# N2a.net
KiCad netlist of a schematic drawn in EAGLE
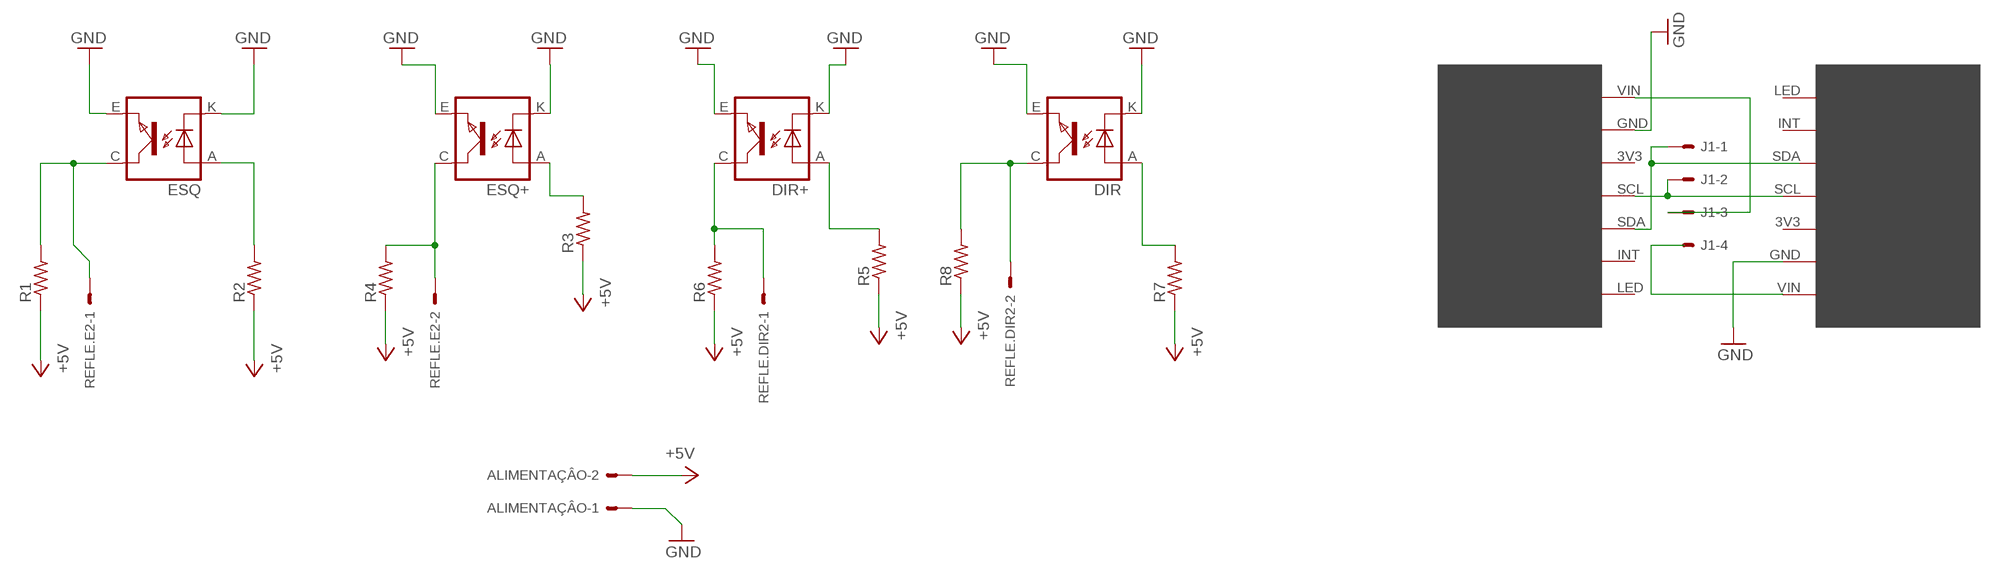
[diagram p0: schematic, sheet 1]

(export (version "E")
  (design (tool "Eeschema 10.0.6"))
  (components
    (comp (ref "ALIMENTAÇÂO")
      (value "CONN_0205-7028")
      (footprint "eagle-import:7395-02")
      (libsource (lib "eagle-import") (part "CONN_0205-7028"))
    )
    (comp (ref "DIR")
      (value "TCRT5000")
      (footprint "eagle-import:TCRT5000")
      (libsource (lib "eagle-import") (part "TCRT5000"))
    )
    (comp (ref "DIR+")
      (value "TCRT5000")
      (footprint "eagle-import:TCRT5000")
      (libsource (lib "eagle-import") (part "TCRT5000"))
    )
    (comp (ref "ESQ")
      (value "TCRT5000")
      (footprint "eagle-import:TCRT5000")
      (libsource (lib "eagle-import") (part "TCRT5000"))
    )
    (comp (ref "ESQ+")
      (value "TCRT5000")
      (footprint "eagle-import:TCRT5000")
      (libsource (lib "eagle-import") (part "TCRT5000"))
    )
    (comp (ref "J1")
      (value "CONN_0405-7048")
      (footprint "eagle-import:7395-04")
      (libsource (lib "eagle-import") (part "CONN_0405-7048"))
    )
    (comp (ref "R1")
      (value "R-US_0204/7")
      (footprint "eagle-import:0204_7")
      (libsource (lib "eagle-import") (part "R-US_0204/7"))
    )
    (comp (ref "R2")
      (value "R-US_0204/7")
      (footprint "eagle-import:0204_7")
      (libsource (lib "eagle-import") (part "R-US_0204/7"))
    )
    (comp (ref "R3")
      (value "R-US_0204/7")
      (footprint "eagle-import:0204_7")
      (libsource (lib "eagle-import") (part "R-US_0204/7"))
    )
    (comp (ref "R4")
      (value "R-US_0204/7")
      (footprint "eagle-import:0204_7")
      (libsource (lib "eagle-import") (part "R-US_0204/7"))
    )
    (comp (ref "R5")
      (value "R-US_0204/7")
      (footprint "eagle-import:0204_7")
      (libsource (lib "eagle-import") (part "R-US_0204/7"))
    )
    (comp (ref "R6")
      (value "R-US_0204/7")
      (footprint "eagle-import:0204_7")
      (libsource (lib "eagle-import") (part "R-US_0204/7"))
    )
    (comp (ref "R7")
      (value "R-US_0204/7")
      (footprint "eagle-import:0204_7")
      (libsource (lib "eagle-import") (part "R-US_0204/7"))
    )
    (comp (ref "R8")
      (value "R-US_0204/7")
      (footprint "eagle-import:0204_7")
      (libsource (lib "eagle-import") (part "R-US_0204/7"))
    )
    (comp (ref "REFLE.DIR2")
      (value "CONN_0205-7028")
      (footprint "eagle-import:7395-02")
      (libsource (lib "eagle-import") (part "CONN_0205-7028"))
    )
    (comp (ref "REFLE.E2")
      (value "CONN_0205-7028")
      (footprint "eagle-import:7395-02")
      (libsource (lib "eagle-import") (part "CONN_0205-7028"))
    )
    (comp (ref "TCS1")
      (value "TCS34725")
      (footprint "eagle-import:TCS34725")
      (libsource (lib "eagle-import") (part "TCS34725"))
    )
    (comp (ref "TCS2")
      (value "TCS34725")
      (footprint "eagle-import:TCS34725")
      (libsource (lib "eagle-import") (part "TCS34725"))
    )
  )
  (nets
    (net (code "1") (name "+5V") (class "Default")
      (node (ref "ALIMENTAÇÂO") (pin "2") (pinfunction "S_2") (pintype "passive"))
      (node (ref "R1") (pin "1") (pinfunction "1_1") (pintype "passive"))
      (node (ref "R2") (pin "1") (pinfunction "1_1") (pintype "passive"))
      (node (ref "R3") (pin "1") (pinfunction "1_1") (pintype "passive"))
      (node (ref "R4") (pin "1") (pinfunction "1_1") (pintype "passive"))
      (node (ref "R5") (pin "1") (pinfunction "1_1") (pintype "passive"))
      (node (ref "R6") (pin "1") (pinfunction "1_1") (pintype "passive"))
      (node (ref "R7") (pin "1") (pinfunction "1_1") (pintype "passive"))
      (node (ref "R8") (pin "1") (pinfunction "1_1") (pintype "passive"))
    )
    (net (code "2") (name "GND") (class "Default")
      (node (ref "ALIMENTAÇÂO") (pin "1") (pinfunction "S_1") (pintype "passive"))
      (node (ref "DIR") (pin "E") (pinfunction "EMITTER_E") (pintype "passive"))
      (node (ref "DIR") (pin "K") (pinfunction "CATHODE_K") (pintype "passive"))
      (node (ref "DIR+") (pin "E") (pinfunction "EMITTER_E") (pintype "passive"))
      (node (ref "DIR+") (pin "K") (pinfunction "CATHODE_K") (pintype "passive"))
      (node (ref "ESQ") (pin "E") (pinfunction "EMITTER_E") (pintype "passive"))
      (node (ref "ESQ") (pin "K") (pinfunction "CATHODE_K") (pintype "passive"))
      (node (ref "ESQ+") (pin "E") (pinfunction "EMITTER_E") (pintype "passive"))
      (node (ref "ESQ+") (pin "K") (pinfunction "CATHODE_K") (pintype "passive"))
      (node (ref "TCS1") (pin "GND") (pinfunction "GND_GND") (pintype "bidirectional"))
      (node (ref "TCS2") (pin "GND") (pinfunction "GND_GND") (pintype "bidirectional"))
    )
    (net (code "3") (name "Net-(DIR+-ANODE)") (class "Default")
      (node (ref "DIR+") (pin "A") (pinfunction "ANODE_A") (pintype "passive"))
      (node (ref "R5") (pin "2") (pinfunction "2_2") (pintype "passive"))
    )
    (net (code "4") (name "Net-(DIR+-COLLECTOR)") (class "Default")
      (node (ref "DIR+") (pin "C") (pinfunction "COLLECTOR_C") (pintype "passive"))
      (node (ref "R6") (pin "2") (pinfunction "2_2") (pintype "passive"))
      (node (ref "REFLE.DIR2") (pin "1") (pinfunction "S_1") (pintype "passive"))
    )
    (net (code "5") (name "Net-(DIR-ANODE)") (class "Default")
      (node (ref "DIR") (pin "A") (pinfunction "ANODE_A") (pintype "passive"))
      (node (ref "R7") (pin "2") (pinfunction "2_2") (pintype "passive"))
    )
    (net (code "6") (name "Net-(DIR-COLLECTOR)") (class "Default")
      (node (ref "DIR") (pin "C") (pinfunction "COLLECTOR_C") (pintype "passive"))
      (node (ref "R8") (pin "2") (pinfunction "2_2") (pintype "passive"))
      (node (ref "REFLE.DIR2") (pin "2") (pinfunction "S_2") (pintype "passive"))
    )
    (net (code "7") (name "Net-(ESQ+-ANODE)") (class "Default")
      (node (ref "ESQ+") (pin "A") (pinfunction "ANODE_A") (pintype "passive"))
      (node (ref "R3") (pin "2") (pinfunction "2_2") (pintype "passive"))
    )
    (net (code "8") (name "Net-(ESQ+-COLLECTOR)") (class "Default")
      (node (ref "ESQ+") (pin "C") (pinfunction "COLLECTOR_C") (pintype "passive"))
      (node (ref "R4") (pin "2") (pinfunction "2_2") (pintype "passive"))
      (node (ref "REFLE.E2") (pin "2") (pinfunction "S_2") (pintype "passive"))
    )
    (net (code "9") (name "Net-(ESQ-ANODE)") (class "Default")
      (node (ref "ESQ") (pin "A") (pinfunction "ANODE_A") (pintype "passive"))
      (node (ref "R2") (pin "2") (pinfunction "2_2") (pintype "passive"))
    )
    (net (code "10") (name "Net-(ESQ-COLLECTOR)") (class "Default")
      (node (ref "ESQ") (pin "C") (pinfunction "COLLECTOR_C") (pintype "passive"))
      (node (ref "R1") (pin "2") (pinfunction "2_2") (pintype "passive"))
      (node (ref "REFLE.E2") (pin "1") (pinfunction "S_1") (pintype "passive"))
    )
    (net (code "11") (name "Net-(J1A-S)") (class "Default")
      (node (ref "J1") (pin "1") (pinfunction "S_1") (pintype "passive"))
      (node (ref "TCS1") (pin "SDA") (pinfunction "SDA_SDA") (pintype "bidirectional"))
    )
    (net (code "12") (name "Net-(J1B-S)") (class "Default")
      (node (ref "J1") (pin "2") (pinfunction "S_2") (pintype "passive"))
      (node (ref "TCS1") (pin "SCL") (pinfunction "SCL_SCL") (pintype "bidirectional"))
      (node (ref "TCS2") (pin "SCL") (pinfunction "SCL_SCL") (pintype "bidirectional"))
    )
    (net (code "13") (name "Net-(J1C-S)") (class "Default")
      (node (ref "J1") (pin "3") (pinfunction "S_3") (pintype "passive"))
      (node (ref "TCS1") (pin "VIN") (pinfunction "VIN_VIN") (pintype "bidirectional"))
    )
    (net (code "14") (name "unconnected-(J1D-S-Pad4)") (class "Default")
      (node (ref "J1") (pin "4") (pinfunction "S_4") (pintype "passive"))
    )
    (net (code "15") (name "unconnected-(TCS1-Pad3V3)") (class "Default")
      (node (ref "TCS1") (pin "3V3") (pinfunction "3V3_3V3") (pintype "bidirectional"))
    )
    (net (code "16") (name "unconnected-(TCS1-PadINT)") (class "Default")
      (node (ref "TCS1") (pin "INT") (pinfunction "INT_INT") (pintype "bidirectional"))
    )
    (net (code "17") (name "unconnected-(TCS1-PadLED)") (class "Default")
      (node (ref "TCS1") (pin "LED") (pinfunction "LED_LED") (pintype "bidirectional"))
    )
    (net (code "18") (name "unconnected-(TCS2-Pad3V3)") (class "Default")
      (node (ref "TCS2") (pin "3V3") (pinfunction "3V3_3V3") (pintype "bidirectional"))
    )
    (net (code "19") (name "unconnected-(TCS2-PadINT)") (class "Default")
      (node (ref "TCS2") (pin "INT") (pinfunction "INT_INT") (pintype "bidirectional"))
    )
    (net (code "20") (name "unconnected-(TCS2-PadLED)") (class "Default")
      (node (ref "TCS2") (pin "LED") (pinfunction "LED_LED") (pintype "bidirectional"))
    )
    (net (code "21") (name "unconnected-(TCS2-PadSDA)") (class "Default")
      (node (ref "TCS2") (pin "SDA") (pinfunction "SDA_SDA") (pintype "bidirectional"))
    )
    (net (code "22") (name "unconnected-(TCS2-PadVIN)") (class "Default")
      (node (ref "TCS2") (pin "VIN") (pinfunction "VIN_VIN") (pintype "bidirectional"))
    )
  )
)
